# microzed_schematic.net
KiCad netlist of a schematic drawn in Altium Designer
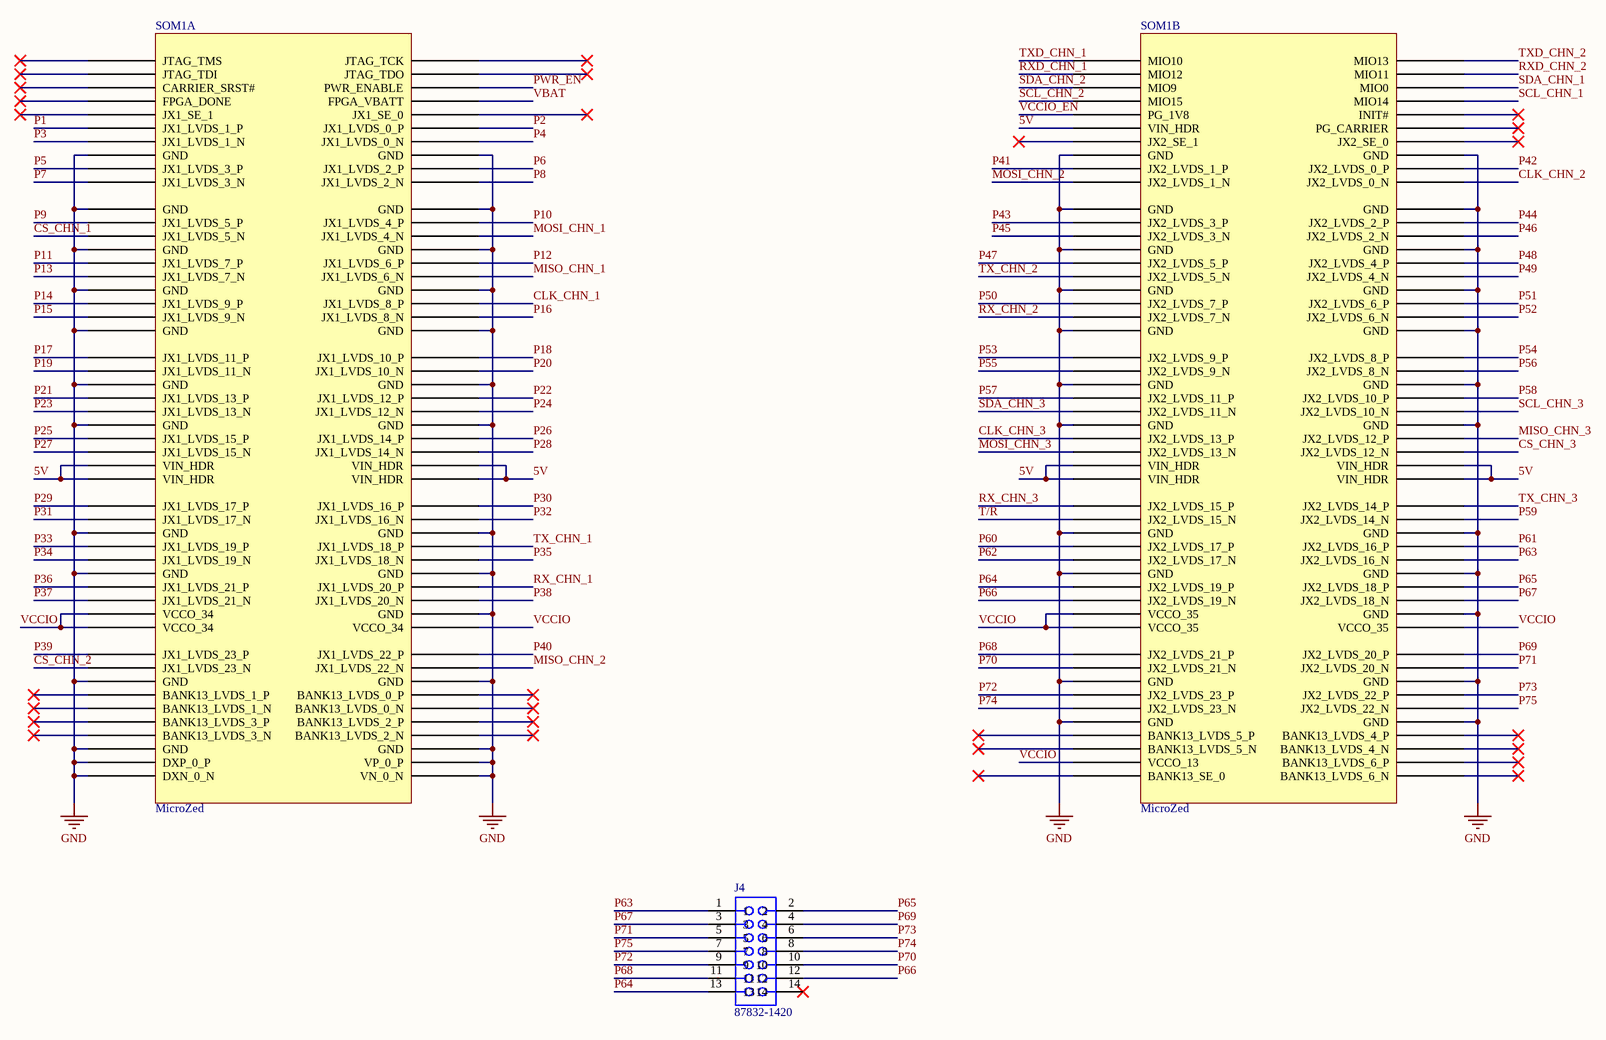
[diagram p0: microzed_schematic.SchDoc]

(export (version "E")
  (design (tool "Eeschema 10.0.6"))
  (components
    (comp (ref "J4")
      (value "87832-1420")
      (footprint "SAMTEC_TSW-107-05-F-D")
      (description "Connector Header Surface Mount 14 position 0.079 _2.00mm_")
      (fields (field (name "MF") "Molex") (field (name "MANUFACTURER PART NUMBER") "TSW-107-05-F-D"))
      (libsource (lib "flatsat_platform_2") (part "87832-1420"))
    )
    (comp (ref "SOM1")
      (value "MicroZed")
      (footprint "MicroZedSOM")
      (description "MicroZed SOM Carrier Footprint")
      (fields (field (name "MANUFACTURER PART NUMBER") "61083-101400LF"))
      (libsource (lib "flatsat_platform_2") (part "MicroZed_SOM"))
    )
  )
  (nets
    (net (code "1") (name "/5V") (class "Default")
      (node (ref "SOM1") (pin "JX1-57") (pinfunction "VIN_HDR_JX1-57") (pintype "passive"))
      (node (ref "SOM1") (pin "JX1-58") (pinfunction "VIN_HDR_JX1-58") (pintype "passive"))
      (node (ref "SOM1") (pin "JX1-59") (pinfunction "VIN_HDR_JX1-59") (pintype "passive"))
      (node (ref "SOM1") (pin "JX1-60") (pinfunction "VIN_HDR_JX1-60") (pintype "passive"))
      (node (ref "SOM1") (pin "JX2-12") (pinfunction "VIN_HDR_JX2-12") (pintype "passive"))
      (node (ref "SOM1") (pin "JX2-57") (pinfunction "VIN_HDR_JX2-57") (pintype "passive"))
      (node (ref "SOM1") (pin "JX2-58") (pinfunction "VIN_HDR_JX2-58") (pintype "passive"))
      (node (ref "SOM1") (pin "JX2-59") (pinfunction "VIN_HDR_JX2-59") (pintype "passive"))
      (node (ref "SOM1") (pin "JX2-60") (pinfunction "VIN_HDR_JX2-60") (pintype "passive"))
    )
    (net (code "2") (name "/CLK_CHN_1") (class "Default")
      (node (ref "SOM1") (pin "JX1-35") (pinfunction "JX1_LVDS_8_P_JX1-35") (pintype "passive"))
    )
    (net (code "3") (name "/CLK_CHN_2") (class "Default")
      (node (ref "SOM1") (pin "JX2-19") (pinfunction "JX2_LVDS_0_N_JX2-19") (pintype "passive"))
    )
    (net (code "4") (name "/CLK_CHN_3") (class "Default")
      (node (ref "SOM1") (pin "JX2-54") (pinfunction "JX2_LVDS_13_P_JX2-54") (pintype "passive"))
    )
    (net (code "5") (name "/CS_CHN_1") (class "Default")
      (node (ref "SOM1") (pin "JX1-26") (pinfunction "JX1_LVDS_5_N_JX1-26") (pintype "passive"))
    )
    (net (code "6") (name "/CS_CHN_2") (class "Default")
      (node (ref "SOM1") (pin "JX1-84") (pinfunction "JX1_LVDS_23_N_JX1-84") (pintype "passive"))
    )
    (net (code "7") (name "/CS_CHN_3") (class "Default")
      (node (ref "SOM1") (pin "JX2-55") (pinfunction "JX2_LVDS_12_N_JX2-55") (pintype "passive"))
    )
    (net (code "8") (name "/MISO_CHN_1") (class "Default")
      (node (ref "SOM1") (pin "JX1-31") (pinfunction "JX1_LVDS_6_N_JX1-31") (pintype "passive"))
    )
    (net (code "9") (name "/MISO_CHN_2") (class "Default")
      (node (ref "SOM1") (pin "JX1-83") (pinfunction "JX1_LVDS_22_N_JX1-83") (pintype "passive"))
    )
    (net (code "10") (name "/MISO_CHN_3") (class "Default")
      (node (ref "SOM1") (pin "JX2-53") (pinfunction "JX2_LVDS_12_P_JX2-53") (pintype "passive"))
    )
    (net (code "11") (name "/MOSI_CHN_1") (class "Default")
      (node (ref "SOM1") (pin "JX1-25") (pinfunction "JX1_LVDS_4_N_JX1-25") (pintype "passive"))
    )
    (net (code "12") (name "/MOSI_CHN_2") (class "Default")
      (node (ref "SOM1") (pin "JX2-20") (pinfunction "JX2_LVDS_1_N_JX2-20") (pintype "passive"))
    )
    (net (code "13") (name "/MOSI_CHN_3") (class "Default")
      (node (ref "SOM1") (pin "JX2-56") (pinfunction "JX2_LVDS_13_N_JX2-56") (pintype "passive"))
    )
    (net (code "14") (name "/P1") (class "Default")
      (node (ref "SOM1") (pin "JX1-12") (pinfunction "JX1_LVDS_1_P_JX1-12") (pintype "passive"))
    )
    (net (code "15") (name "/P2") (class "Default")
      (node (ref "SOM1") (pin "JX1-11") (pinfunction "JX1_LVDS_0_P_JX1-11") (pintype "passive"))
    )
    (net (code "16") (name "/P3") (class "Default")
      (node (ref "SOM1") (pin "JX1-14") (pinfunction "JX1_LVDS_1_N_JX1-14") (pintype "passive"))
    )
    (net (code "17") (name "/P4") (class "Default")
      (node (ref "SOM1") (pin "JX1-13") (pinfunction "JX1_LVDS_0_N_JX1-13") (pintype "passive"))
    )
    (net (code "18") (name "/P5") (class "Default")
      (node (ref "SOM1") (pin "JX1-18") (pinfunction "JX1_LVDS_3_P_JX1-18") (pintype "passive"))
    )
    (net (code "19") (name "/P6") (class "Default")
      (node (ref "SOM1") (pin "JX1-17") (pinfunction "JX1_LVDS_2_P_JX1-17") (pintype "passive"))
    )
    (net (code "20") (name "/P7") (class "Default")
      (node (ref "SOM1") (pin "JX1-20") (pinfunction "JX1_LVDS_3_N_JX1-20") (pintype "passive"))
    )
    (net (code "21") (name "/P8") (class "Default")
      (node (ref "SOM1") (pin "JX1-19") (pinfunction "JX1_LVDS_2_N_JX1-19") (pintype "passive"))
    )
    (net (code "22") (name "/P9") (class "Default")
      (node (ref "SOM1") (pin "JX1-24") (pinfunction "JX1_LVDS_5_P_JX1-24") (pintype "passive"))
    )
    (net (code "23") (name "/P10") (class "Default")
      (node (ref "SOM1") (pin "JX1-23") (pinfunction "JX1_LVDS_4_P_JX1-23") (pintype "passive"))
    )
    (net (code "24") (name "/P11") (class "Default")
      (node (ref "SOM1") (pin "JX1-30") (pinfunction "JX1_LVDS_7_P_JX1-30") (pintype "passive"))
    )
    (net (code "25") (name "/P12") (class "Default")
      (node (ref "SOM1") (pin "JX1-29") (pinfunction "JX1_LVDS_6_P_JX1-29") (pintype "passive"))
    )
    (net (code "26") (name "/P13") (class "Default")
      (node (ref "SOM1") (pin "JX1-32") (pinfunction "JX1_LVDS_7_N_JX1-32") (pintype "passive"))
    )
    (net (code "27") (name "/P14") (class "Default")
      (node (ref "SOM1") (pin "JX1-36") (pinfunction "JX1_LVDS_9_P_JX1-36") (pintype "passive"))
    )
    (net (code "28") (name "/P15") (class "Default")
      (node (ref "SOM1") (pin "JX1-38") (pinfunction "JX1_LVDS_9_N_JX1-38") (pintype "passive"))
    )
    (net (code "29") (name "/P16") (class "Default")
      (node (ref "SOM1") (pin "JX1-37") (pinfunction "JX1_LVDS_8_N_JX1-37") (pintype "passive"))
    )
    (net (code "30") (name "/P17") (class "Default")
      (node (ref "SOM1") (pin "JX1-42") (pinfunction "JX1_LVDS_11_P_JX1-42") (pintype "passive"))
    )
    (net (code "31") (name "/P18") (class "Default")
      (node (ref "SOM1") (pin "JX1-41") (pinfunction "JX1_LVDS_10_P_JX1-41") (pintype "passive"))
    )
    (net (code "32") (name "/P19") (class "Default")
      (node (ref "SOM1") (pin "JX1-44") (pinfunction "JX1_LVDS_11_N_JX1-44") (pintype "passive"))
    )
    (net (code "33") (name "/P20") (class "Default")
      (node (ref "SOM1") (pin "JX1-43") (pinfunction "JX1_LVDS_10_N_JX1-43") (pintype "passive"))
    )
    (net (code "34") (name "/P21") (class "Default")
      (node (ref "SOM1") (pin "JX1-48") (pinfunction "JX1_LVDS_13_P_JX1-48") (pintype "passive"))
    )
    (net (code "35") (name "/P22") (class "Default")
      (node (ref "SOM1") (pin "JX1-47") (pinfunction "JX1_LVDS_12_P_JX1-47") (pintype "passive"))
    )
    (net (code "36") (name "/P23") (class "Default")
      (node (ref "SOM1") (pin "JX1-50") (pinfunction "JX1_LVDS_13_N_JX1-50") (pintype "passive"))
    )
    (net (code "37") (name "/P24") (class "Default")
      (node (ref "SOM1") (pin "JX1-49") (pinfunction "JX1_LVDS_12_N_JX1-49") (pintype "passive"))
    )
    (net (code "38") (name "/P25") (class "Default")
      (node (ref "SOM1") (pin "JX1-54") (pinfunction "JX1_LVDS_15_P_JX1-54") (pintype "passive"))
    )
    (net (code "39") (name "/P26") (class "Default")
      (node (ref "SOM1") (pin "JX1-53") (pinfunction "JX1_LVDS_14_P_JX1-53") (pintype "passive"))
    )
    (net (code "40") (name "/P27") (class "Default")
      (node (ref "SOM1") (pin "JX1-56") (pinfunction "JX1_LVDS_15_N_JX1-56") (pintype "passive"))
    )
    (net (code "41") (name "/P28") (class "Default")
      (node (ref "SOM1") (pin "JX1-55") (pinfunction "JX1_LVDS_14_N_JX1-55") (pintype "passive"))
    )
    (net (code "42") (name "/P29") (class "Default")
      (node (ref "SOM1") (pin "JX1-62") (pinfunction "JX1_LVDS_17_P_JX1-62") (pintype "passive"))
    )
    (net (code "43") (name "/P30") (class "Default")
      (node (ref "SOM1") (pin "JX1-61") (pinfunction "JX1_LVDS_16_P_JX1-61") (pintype "passive"))
    )
    (net (code "44") (name "/P31") (class "Default")
      (node (ref "SOM1") (pin "JX1-64") (pinfunction "JX1_LVDS_17_N_JX1-64") (pintype "passive"))
    )
    (net (code "45") (name "/P32") (class "Default")
      (node (ref "SOM1") (pin "JX1-63") (pinfunction "JX1_LVDS_16_N_JX1-63") (pintype "passive"))
    )
    (net (code "46") (name "/P33") (class "Default")
      (node (ref "SOM1") (pin "JX1-68") (pinfunction "JX1_LVDS_19_P_JX1-68") (pintype "passive"))
    )
    (net (code "47") (name "/P34") (class "Default")
      (node (ref "SOM1") (pin "JX1-70") (pinfunction "JX1_LVDS_19_N_JX1-70") (pintype "passive"))
    )
    (net (code "48") (name "/P35") (class "Default")
      (node (ref "SOM1") (pin "JX1-69") (pinfunction "JX1_LVDS_18_N_JX1-69") (pintype "passive"))
    )
    (net (code "49") (name "/P36") (class "Default")
      (node (ref "SOM1") (pin "JX1-74") (pinfunction "JX1_LVDS_21_P_JX1-74") (pintype "passive"))
    )
    (net (code "50") (name "/P37") (class "Default")
      (node (ref "SOM1") (pin "JX1-76") (pinfunction "JX1_LVDS_21_N_JX1-76") (pintype "passive"))
    )
    (net (code "51") (name "/P38") (class "Default")
      (node (ref "SOM1") (pin "JX1-75") (pinfunction "JX1_LVDS_20_N_JX1-75") (pintype "passive"))
    )
    (net (code "52") (name "/P39") (class "Default")
      (node (ref "SOM1") (pin "JX1-82") (pinfunction "JX1_LVDS_23_P_JX1-82") (pintype "passive"))
    )
    (net (code "53") (name "/P40") (class "Default")
      (node (ref "SOM1") (pin "JX1-81") (pinfunction "JX1_LVDS_22_P_JX1-81") (pintype "passive"))
    )
    (net (code "54") (name "/P41") (class "Default")
      (node (ref "SOM1") (pin "JX2-18") (pinfunction "JX2_LVDS_1_P_JX2-18") (pintype "passive"))
    )
    (net (code "55") (name "/P42") (class "Default")
      (node (ref "SOM1") (pin "JX2-17") (pinfunction "JX2_LVDS_0_P_JX2-17") (pintype "passive"))
    )
    (net (code "56") (name "/P43") (class "Default")
      (node (ref "SOM1") (pin "JX2-24") (pinfunction "JX2_LVDS_3_P_JX2-24") (pintype "passive"))
    )
    (net (code "57") (name "/P44") (class "Default")
      (node (ref "SOM1") (pin "JX2-23") (pinfunction "JX2_LVDS_2_P_JX2-23") (pintype "passive"))
    )
    (net (code "58") (name "/P45") (class "Default")
      (node (ref "SOM1") (pin "JX2-26") (pinfunction "JX2_LVDS_3_N_JX2-26") (pintype "passive"))
    )
    (net (code "59") (name "/P46") (class "Default")
      (node (ref "SOM1") (pin "JX2-25") (pinfunction "JX2_LVDS_2_N_JX2-25") (pintype "passive"))
    )
    (net (code "60") (name "/P47") (class "Default")
      (node (ref "SOM1") (pin "JX2-30") (pinfunction "JX2_LVDS_5_P_JX2-30") (pintype "passive"))
    )
    (net (code "61") (name "/P48") (class "Default")
      (node (ref "SOM1") (pin "JX2-29") (pinfunction "JX2_LVDS_4_P_JX2-29") (pintype "passive"))
    )
    (net (code "62") (name "/P49") (class "Default")
      (node (ref "SOM1") (pin "JX2-31") (pinfunction "JX2_LVDS_4_N_JX2-31") (pintype "passive"))
    )
    (net (code "63") (name "/P50") (class "Default")
      (node (ref "SOM1") (pin "JX2-36") (pinfunction "JX2_LVDS_7_P_JX2-36") (pintype "passive"))
    )
    (net (code "64") (name "/P51") (class "Default")
      (node (ref "SOM1") (pin "JX2-35") (pinfunction "JX2_LVDS_6_P_JX2-35") (pintype "passive"))
    )
    (net (code "65") (name "/P52") (class "Default")
      (node (ref "SOM1") (pin "JX2-37") (pinfunction "JX2_LVDS_6_N_JX2-37") (pintype "passive"))
    )
    (net (code "66") (name "/P53") (class "Default")
      (node (ref "SOM1") (pin "JX2-42") (pinfunction "JX2_LVDS_9_P_JX2-42") (pintype "passive"))
    )
    (net (code "67") (name "/P54") (class "Default")
      (node (ref "SOM1") (pin "JX2-41") (pinfunction "JX2_LVDS_8_P_JX2-41") (pintype "passive"))
    )
    (net (code "68") (name "/P55") (class "Default")
      (node (ref "SOM1") (pin "JX2-44") (pinfunction "JX2_LVDS_9_N_JX2-44") (pintype "passive"))
    )
    (net (code "69") (name "/P56") (class "Default")
      (node (ref "SOM1") (pin "JX2-43") (pinfunction "JX2_LVDS_8_N_JX2-43") (pintype "passive"))
    )
    (net (code "70") (name "/P57") (class "Default")
      (node (ref "SOM1") (pin "JX2-48") (pinfunction "JX2_LVDS_11_P_JX2-48") (pintype "passive"))
    )
    (net (code "71") (name "/P58") (class "Default")
      (node (ref "SOM1") (pin "JX2-47") (pinfunction "JX2_LVDS_10_P_JX2-47") (pintype "passive"))
    )
    (net (code "72") (name "/P59") (class "Default")
      (node (ref "SOM1") (pin "JX2-63") (pinfunction "JX2_LVDS_14_N_JX2-63") (pintype "passive"))
    )
    (net (code "73") (name "/P60") (class "Default")
      (node (ref "SOM1") (pin "JX2-68") (pinfunction "JX2_LVDS_17_P_JX2-68") (pintype "passive"))
    )
    (net (code "74") (name "/P61") (class "Default")
      (node (ref "SOM1") (pin "JX2-67") (pinfunction "JX2_LVDS_16_P_JX2-67") (pintype "passive"))
    )
    (net (code "75") (name "/P62") (class "Default")
      (node (ref "SOM1") (pin "JX2-70") (pinfunction "JX2_LVDS_17_N_JX2-70") (pintype "passive"))
    )
    (net (code "76") (name "/P63") (class "Default")
      (node (ref "J4") (pin "1") (pinfunction "1_1") (pintype "passive"))
      (node (ref "SOM1") (pin "JX2-69") (pinfunction "JX2_LVDS_16_N_JX2-69") (pintype "passive"))
    )
    (net (code "77") (name "/P64") (class "Default")
      (node (ref "J4") (pin "13") (pinfunction "13_13") (pintype "passive"))
      (node (ref "SOM1") (pin "JX2-74") (pinfunction "JX2_LVDS_19_P_JX2-74") (pintype "passive"))
    )
    (net (code "78") (name "/P65") (class "Default")
      (node (ref "J4") (pin "2") (pinfunction "2_2") (pintype "passive"))
      (node (ref "SOM1") (pin "JX2-73") (pinfunction "JX2_LVDS_18_P_JX2-73") (pintype "passive"))
    )
    (net (code "79") (name "/P66") (class "Default")
      (node (ref "J4") (pin "12") (pinfunction "12_12") (pintype "passive"))
      (node (ref "SOM1") (pin "JX2-76") (pinfunction "JX2_LVDS_19_N_JX2-76") (pintype "passive"))
    )
    (net (code "80") (name "/P67") (class "Default")
      (node (ref "J4") (pin "3") (pinfunction "3_3") (pintype "passive"))
      (node (ref "SOM1") (pin "JX2-75") (pinfunction "JX2_LVDS_18_N_JX2-75") (pintype "passive"))
    )
    (net (code "81") (name "/P68") (class "Default")
      (node (ref "J4") (pin "11") (pinfunction "11_11") (pintype "passive"))
      (node (ref "SOM1") (pin "JX2-82") (pinfunction "JX2_LVDS_21_P_JX2-82") (pintype "passive"))
    )
    (net (code "82") (name "/P69") (class "Default")
      (node (ref "J4") (pin "4") (pinfunction "4_4") (pintype "passive"))
      (node (ref "SOM1") (pin "JX2-81") (pinfunction "JX2_LVDS_20_P_JX2-81") (pintype "passive"))
    )
    (net (code "83") (name "/P70") (class "Default")
      (node (ref "J4") (pin "10") (pinfunction "10_10") (pintype "passive"))
      (node (ref "SOM1") (pin "JX2-84") (pinfunction "JX2_LVDS_21_N_JX2-84") (pintype "passive"))
    )
    (net (code "84") (name "/P71") (class "Default")
      (node (ref "J4") (pin "5") (pinfunction "5_5") (pintype "passive"))
      (node (ref "SOM1") (pin "JX2-83") (pinfunction "JX2_LVDS_20_N_JX2-83") (pintype "passive"))
    )
    (net (code "85") (name "/P72") (class "Default")
      (node (ref "J4") (pin "9") (pinfunction "9_9") (pintype "passive"))
      (node (ref "SOM1") (pin "JX2-88") (pinfunction "JX2_LVDS_23_P_JX2-88") (pintype "passive"))
    )
    (net (code "86") (name "/P73") (class "Default")
      (node (ref "J4") (pin "6") (pinfunction "6_6") (pintype "passive"))
      (node (ref "SOM1") (pin "JX2-87") (pinfunction "JX2_LVDS_22_P_JX2-87") (pintype "passive"))
    )
    (net (code "87") (name "/P74") (class "Default")
      (node (ref "J4") (pin "8") (pinfunction "8_8") (pintype "passive"))
      (node (ref "SOM1") (pin "JX2-90") (pinfunction "JX2_LVDS_23_N_JX2-90") (pintype "passive"))
    )
    (net (code "88") (name "/P75") (class "Default")
      (node (ref "J4") (pin "7") (pinfunction "7_7") (pintype "passive"))
      (node (ref "SOM1") (pin "JX2-89") (pinfunction "JX2_LVDS_22_N_JX2-89") (pintype "passive"))
    )
    (net (code "89") (name "/PWR_EN") (class "Default")
      (node (ref "SOM1") (pin "JX1-5") (pinfunction "PWR_ENABLE_JX1-5") (pintype "passive"))
    )
    (net (code "90") (name "/RXD_CHN_1") (class "Default")
      (node (ref "SOM1") (pin "JX2-4") (pinfunction "MIO12_JX2-4") (pintype "passive"))
    )
    (net (code "91") (name "/RXD_CHN_2") (class "Default")
      (node (ref "SOM1") (pin "JX2-3") (pinfunction "MIO11_JX2-3") (pintype "passive"))
    )
    (net (code "92") (name "/RX_CHN_1") (class "Default")
      (node (ref "SOM1") (pin "JX1-73") (pinfunction "JX1_LVDS_20_P_JX1-73") (pintype "passive"))
    )
    (net (code "93") (name "/RX_CHN_2") (class "Default")
      (node (ref "SOM1") (pin "JX2-38") (pinfunction "JX2_LVDS_7_N_JX2-38") (pintype "passive"))
    )
    (net (code "94") (name "/RX_CHN_3") (class "Default")
      (node (ref "SOM1") (pin "JX2-62") (pinfunction "JX2_LVDS_15_P_JX2-62") (pintype "passive"))
    )
    (net (code "95") (name "/SCL_CHN_1") (class "Default")
      (node (ref "SOM1") (pin "JX2-7") (pinfunction "MIO14_JX2-7") (pintype "passive"))
    )
    (net (code "96") (name "/SCL_CHN_2") (class "Default")
      (node (ref "SOM1") (pin "JX2-8") (pinfunction "MIO15_JX2-8") (pintype "passive"))
    )
    (net (code "97") (name "/SCL_CHN_3") (class "Default")
      (node (ref "SOM1") (pin "JX2-49") (pinfunction "JX2_LVDS_10_N_JX2-49") (pintype "passive"))
    )
    (net (code "98") (name "/SDA_CHN_1") (class "Default")
      (node (ref "SOM1") (pin "JX2-5") (pinfunction "MIO0_JX2-5") (pintype "passive"))
    )
    (net (code "99") (name "/SDA_CHN_2") (class "Default")
      (node (ref "SOM1") (pin "JX2-6") (pinfunction "MIO9_JX2-6") (pintype "passive"))
    )
    (net (code "100") (name "/SDA_CHN_3") (class "Default")
      (node (ref "SOM1") (pin "JX2-50") (pinfunction "JX2_LVDS_11_N_JX2-50") (pintype "passive"))
    )
    (net (code "101") (name "/TXD_CHN_1") (class "Default")
      (node (ref "SOM1") (pin "JX2-2") (pinfunction "MIO10_JX2-2") (pintype "passive"))
    )
    (net (code "102") (name "/TXD_CHN_2") (class "Default")
      (node (ref "SOM1") (pin "JX2-1") (pinfunction "MIO13_JX2-1") (pintype "passive"))
    )
    (net (code "103") (name "/TX_CHN_1") (class "Default")
      (node (ref "SOM1") (pin "JX1-67") (pinfunction "JX1_LVDS_18_P_JX1-67") (pintype "passive"))
    )
    (net (code "104") (name "/TX_CHN_2") (class "Default")
      (node (ref "SOM1") (pin "JX2-32") (pinfunction "JX2_LVDS_5_N_JX2-32") (pintype "passive"))
    )
    (net (code "105") (name "/TX_CHN_3") (class "Default")
      (node (ref "SOM1") (pin "JX2-61") (pinfunction "JX2_LVDS_14_P_JX2-61") (pintype "passive"))
    )
    (net (code "106") (name "/T{slash}R") (class "Default")
      (node (ref "SOM1") (pin "JX2-64") (pinfunction "JX2_LVDS_15_N_JX2-64") (pintype "passive"))
    )
    (net (code "107") (name "/VBAT") (class "Default")
      (node (ref "SOM1") (pin "JX1-7") (pinfunction "FPGA_VBATT_JX1-7") (pintype "passive"))
    )
    (net (code "108") (name "/VCCIO") (class "Default")
      (node (ref "SOM1") (pin "JX1-78") (pinfunction "VCCO_34_JX1-78") (pintype "passive"))
      (node (ref "SOM1") (pin "JX1-79") (pinfunction "VCCO_34_JX1-79") (pintype "passive"))
      (node (ref "SOM1") (pin "JX1-80") (pinfunction "VCCO_34_JX1-80") (pintype "passive"))
      (node (ref "SOM1") (pin "JX2-78") (pinfunction "VCCO_35_JX2-78") (pintype "passive"))
      (node (ref "SOM1") (pin "JX2-79") (pinfunction "VCCO_35_JX2-79") (pintype "passive"))
      (node (ref "SOM1") (pin "JX2-80") (pinfunction "VCCO_35_JX2-80") (pintype "passive"))
      (node (ref "SOM1") (pin "JX2-98") (pinfunction "VCCO_13_JX2-98") (pintype "passive"))
    )
    (net (code "109") (name "/VCCIO_EN") (class "Default")
      (node (ref "SOM1") (pin "JX2-10") (pinfunction "PG_1V8_JX2-10") (pintype "passive"))
    )
    (net (code "110") (name "GND") (class "Default")
      (node (ref "SOM1") (pin "JX1-100") (pinfunction "DXN_0_N_JX1-100") (pintype "passive"))
      (node (ref "SOM1") (pin "JX1-15") (pinfunction "GND_JX1-15") (pintype "passive"))
      (node (ref "SOM1") (pin "JX1-16") (pinfunction "GND_JX1-16") (pintype "passive"))
      (node (ref "SOM1") (pin "JX1-21") (pinfunction "GND_JX1-21") (pintype "passive"))
      (node (ref "SOM1") (pin "JX1-22") (pinfunction "GND_JX1-22") (pintype "passive"))
      (node (ref "SOM1") (pin "JX1-27") (pinfunction "GND_JX1-27") (pintype "passive"))
      (node (ref "SOM1") (pin "JX1-28") (pinfunction "GND_JX1-28") (pintype "passive"))
      (node (ref "SOM1") (pin "JX1-33") (pinfunction "GND_JX1-33") (pintype "passive"))
      (node (ref "SOM1") (pin "JX1-34") (pinfunction "GND_JX1-34") (pintype "passive"))
      (node (ref "SOM1") (pin "JX1-39") (pinfunction "GND_JX1-39") (pintype "passive"))
      (node (ref "SOM1") (pin "JX1-40") (pinfunction "GND_JX1-40") (pintype "passive"))
      (node (ref "SOM1") (pin "JX1-45") (pinfunction "GND_JX1-45") (pintype "passive"))
      (node (ref "SOM1") (pin "JX1-46") (pinfunction "GND_JX1-46") (pintype "passive"))
      (node (ref "SOM1") (pin "JX1-51") (pinfunction "GND_JX1-51") (pintype "passive"))
      (node (ref "SOM1") (pin "JX1-52") (pinfunction "GND_JX1-52") (pintype "passive"))
      (node (ref "SOM1") (pin "JX1-65") (pinfunction "GND_JX1-65") (pintype "passive"))
      (node (ref "SOM1") (pin "JX1-66") (pinfunction "GND_JX1-66") (pintype "passive"))
      (node (ref "SOM1") (pin "JX1-71") (pinfunction "GND_JX1-71") (pintype "passive"))
      (node (ref "SOM1") (pin "JX1-72") (pinfunction "GND_JX1-72") (pintype "passive"))
      (node (ref "SOM1") (pin "JX1-77") (pinfunction "GND_JX1-77") (pintype "passive"))
      (node (ref "SOM1") (pin "JX1-85") (pinfunction "GND_JX1-85") (pintype "passive"))
      (node (ref "SOM1") (pin "JX1-86") (pinfunction "GND_JX1-86") (pintype "passive"))
      (node (ref "SOM1") (pin "JX1-95") (pinfunction "GND_JX1-95") (pintype "passive"))
      (node (ref "SOM1") (pin "JX1-96") (pinfunction "GND_JX1-96") (pintype "passive"))
      (node (ref "SOM1") (pin "JX1-97") (pinfunction "VP_0_P_JX1-97") (pintype "passive"))
      (node (ref "SOM1") (pin "JX1-98") (pinfunction "DXP_0_P_JX1-98") (pintype "passive"))
      (node (ref "SOM1") (pin "JX1-99") (pinfunction "VN_0_N_JX1-99") (pintype "passive"))
      (node (ref "SOM1") (pin "JX2-15") (pinfunction "GND_JX2-15") (pintype "passive"))
      (node (ref "SOM1") (pin "JX2-16") (pinfunction "GND_JX2-16") (pintype "passive"))
      (node (ref "SOM1") (pin "JX2-21") (pinfunction "GND_JX2-21") (pintype "passive"))
      (node (ref "SOM1") (pin "JX2-22") (pinfunction "GND_JX2-22") (pintype "passive"))
      (node (ref "SOM1") (pin "JX2-27") (pinfunction "GND_JX2-27") (pintype "passive"))
      (node (ref "SOM1") (pin "JX2-28") (pinfunction "GND_JX2-28") (pintype "passive"))
      (node (ref "SOM1") (pin "JX2-33") (pinfunction "GND_JX2-33") (pintype "passive"))
      (node (ref "SOM1") (pin "JX2-34") (pinfunction "GND_JX2-34") (pintype "passive"))
      (node (ref "SOM1") (pin "JX2-39") (pinfunction "GND_JX2-39") (pintype "passive"))
      (node (ref "SOM1") (pin "JX2-40") (pinfunction "GND_JX2-40") (pintype "passive"))
      (node (ref "SOM1") (pin "JX2-45") (pinfunction "GND_JX2-45") (pintype "passive"))
      (node (ref "SOM1") (pin "JX2-46") (pinfunction "GND_JX2-46") (pintype "passive"))
      (node (ref "SOM1") (pin "JX2-51") (pinfunction "GND_JX2-51") (pintype "passive"))
      (node (ref "SOM1") (pin "JX2-52") (pinfunction "GND_JX2-52") (pintype "passive"))
      (node (ref "SOM1") (pin "JX2-65") (pinfunction "GND_JX2-65") (pintype "passive"))
      (node (ref "SOM1") (pin "JX2-66") (pinfunction "GND_JX2-66") (pintype "passive"))
      (node (ref "SOM1") (pin "JX2-71") (pinfunction "GND_JX2-71") (pintype "passive"))
      (node (ref "SOM1") (pin "JX2-72") (pinfunction "GND_JX2-72") (pintype "passive"))
      (node (ref "SOM1") (pin "JX2-77") (pinfunction "GND_JX2-77") (pintype "passive"))
      (node (ref "SOM1") (pin "JX2-85") (pinfunction "GND_JX2-85") (pintype "passive"))
      (node (ref "SOM1") (pin "JX2-86") (pinfunction "GND_JX2-86") (pintype "passive"))
      (node (ref "SOM1") (pin "JX2-91") (pinfunction "GND_JX2-91") (pintype "passive"))
      (node (ref "SOM1") (pin "JX2-92") (pinfunction "GND_JX2-92") (pintype "passive"))
    )
    (net (code "111") (name "unconnected-(J4-Pad14)") (class "Default")
      (node (ref "J4") (pin "14") (pinfunction "14_14") (pintype "passive+no_connect"))
    )
    (net (code "112") (name "unconnected-(SOM1A-BANK13_LVDS_0_N-PadJX1-89)") (class "Default")
      (node (ref "SOM1") (pin "JX1-89") (pinfunction "BANK13_LVDS_0_N_JX1-89") (pintype "passive+no_connect"))
    )
    (net (code "113") (name "unconnected-(SOM1A-BANK13_LVDS_0_P-PadJX1-87)") (class "Default")
      (node (ref "SOM1") (pin "JX1-87") (pinfunction "BANK13_LVDS_0_P_JX1-87") (pintype "passive+no_connect"))
    )
    (net (code "114") (name "unconnected-(SOM1A-BANK13_LVDS_1_N-PadJX1-90)") (class "Default")
      (node (ref "SOM1") (pin "JX1-90") (pinfunction "BANK13_LVDS_1_N_JX1-90") (pintype "passive+no_connect"))
    )
    (net (code "115") (name "unconnected-(SOM1A-BANK13_LVDS_1_P-PadJX1-88)") (class "Default")
      (node (ref "SOM1") (pin "JX1-88") (pinfunction "BANK13_LVDS_1_P_JX1-88") (pintype "passive+no_connect"))
    )
    (net (code "116") (name "unconnected-(SOM1A-BANK13_LVDS_2_N-PadJX1-93)") (class "Default")
      (node (ref "SOM1") (pin "JX1-93") (pinfunction "BANK13_LVDS_2_N_JX1-93") (pintype "passive+no_connect"))
    )
    (net (code "117") (name "unconnected-(SOM1A-BANK13_LVDS_2_P-PadJX1-91)") (class "Default")
      (node (ref "SOM1") (pin "JX1-91") (pinfunction "BANK13_LVDS_2_P_JX1-91") (pintype "passive+no_connect"))
    )
    (net (code "118") (name "unconnected-(SOM1A-BANK13_LVDS_3_N-PadJX1-94)") (class "Default")
      (node (ref "SOM1") (pin "JX1-94") (pinfunction "BANK13_LVDS_3_N_JX1-94") (pintype "passive+no_connect"))
    )
    (net (code "119") (name "unconnected-(SOM1A-BANK13_LVDS_3_P-PadJX1-92)") (class "Default")
      (node (ref "SOM1") (pin "JX1-92") (pinfunction "BANK13_LVDS_3_P_JX1-92") (pintype "passive+no_connect"))
    )
    (net (code "120") (name "unconnected-(SOM1A-CARRIER_SRST#-PadJX1-6)") (class "Default")
      (node (ref "SOM1") (pin "JX1-6") (pinfunction "CARRIER_SRST#_JX1-6") (pintype "passive+no_connect"))
    )
    (net (code "121") (name "unconnected-(SOM1A-FPGA_DONE-PadJX1-8)") (class "Default")
      (node (ref "SOM1") (pin "JX1-8") (pinfunction "FPGA_DONE_JX1-8") (pintype "passive+no_connect"))
    )
    (net (code "122") (name "unconnected-(SOM1A-JTAG_TCK-PadJX1-1)") (class "Default")
      (node (ref "SOM1") (pin "JX1-1") (pinfunction "JTAG_TCK_JX1-1") (pintype "passive+no_connect"))
    )
    (net (code "123") (name "unconnected-(SOM1A-JTAG_TDI-PadJX1-4)") (class "Default")
      (node (ref "SOM1") (pin "JX1-4") (pinfunction "JTAG_TDI_JX1-4") (pintype "passive+no_connect"))
    )
    (net (code "124") (name "unconnected-(SOM1A-JTAG_TDO-PadJX1-3)") (class "Default")
      (node (ref "SOM1") (pin "JX1-3") (pinfunction "JTAG_TDO_JX1-3") (pintype "passive+no_connect"))
    )
    (net (code "125") (name "unconnected-(SOM1A-JTAG_TMS-PadJX1-2)") (class "Default")
      (node (ref "SOM1") (pin "JX1-2") (pinfunction "JTAG_TMS_JX1-2") (pintype "passive+no_connect"))
    )
    (net (code "126") (name "unconnected-(SOM1A-JX1_SE_0-PadJX1-9)") (class "Default")
      (node (ref "SOM1") (pin "JX1-9") (pinfunction "JX1_SE_0_JX1-9") (pintype "passive+no_connect"))
    )
    (net (code "127") (name "unconnected-(SOM1A-JX1_SE_1-PadJX1-10)") (class "Default")
      (node (ref "SOM1") (pin "JX1-10") (pinfunction "JX1_SE_1_JX1-10") (pintype "passive+no_connect"))
    )
    (net (code "128") (name "unconnected-(SOM1B-BANK13_LVDS_4_N-PadJX2-95)") (class "Default")
      (node (ref "SOM1") (pin "JX2-95") (pinfunction "BANK13_LVDS_4_N_JX2-95") (pintype "passive+no_connect"))
    )
    (net (code "129") (name "unconnected-(SOM1B-BANK13_LVDS_4_P-PadJX2-93)") (class "Default")
      (node (ref "SOM1") (pin "JX2-93") (pinfunction "BANK13_LVDS_4_P_JX2-93") (pintype "passive+no_connect"))
    )
    (net (code "130") (name "unconnected-(SOM1B-BANK13_LVDS_5_N-PadJX2-96)") (class "Default")
      (node (ref "SOM1") (pin "JX2-96") (pinfunction "BANK13_LVDS_5_N_JX2-96") (pintype "passive+no_connect"))
    )
    (net (code "131") (name "unconnected-(SOM1B-BANK13_LVDS_5_P-PadJX2-94)") (class "Default")
      (node (ref "SOM1") (pin "JX2-94") (pinfunction "BANK13_LVDS_5_P_JX2-94") (pintype "passive+no_connect"))
    )
    (net (code "132") (name "unconnected-(SOM1B-BANK13_LVDS_6_N-PadJX2-99)") (class "Default")
      (node (ref "SOM1") (pin "JX2-99") (pinfunction "BANK13_LVDS_6_N_JX2-99") (pintype "passive+no_connect"))
    )
    (net (code "133") (name "unconnected-(SOM1B-BANK13_LVDS_6_P-PadJX2-97)") (class "Default")
      (node (ref "SOM1") (pin "JX2-97") (pinfunction "BANK13_LVDS_6_P_JX2-97") (pintype "passive+no_connect"))
    )
    (net (code "134") (name "unconnected-(SOM1B-BANK13_SE_0-PadJX2-100)") (class "Default")
      (node (ref "SOM1") (pin "JX2-100") (pinfunction "BANK13_SE_0_JX2-100") (pintype "passive+no_connect"))
    )
    (net (code "135") (name "unconnected-(SOM1B-INIT#-PadJX2-9)") (class "Default")
      (node (ref "SOM1") (pin "JX2-9") (pinfunction "INIT#_JX2-9") (pintype "passive+no_connect"))
    )
    (net (code "136") (name "unconnected-(SOM1B-JX2_SE_0-PadJX2-13)") (class "Default")
      (node (ref "SOM1") (pin "JX2-13") (pinfunction "JX2_SE_0_JX2-13") (pintype "passive+no_connect"))
    )
    (net (code "137") (name "unconnected-(SOM1B-JX2_SE_1-PadJX2-14)") (class "Default")
      (node (ref "SOM1") (pin "JX2-14") (pinfunction "JX2_SE_1_JX2-14") (pintype "passive+no_connect"))
    )
    (net (code "138") (name "unconnected-(SOM1B-PG_CARRIER-PadJX2-11)") (class "Default")
      (node (ref "SOM1") (pin "JX2-11") (pinfunction "PG_CARRIER_JX2-11") (pintype "passive+no_connect"))
    )
  )
)
